# InputCircuits.net
KiCad netlist of a schematic drawn in Altium Designer
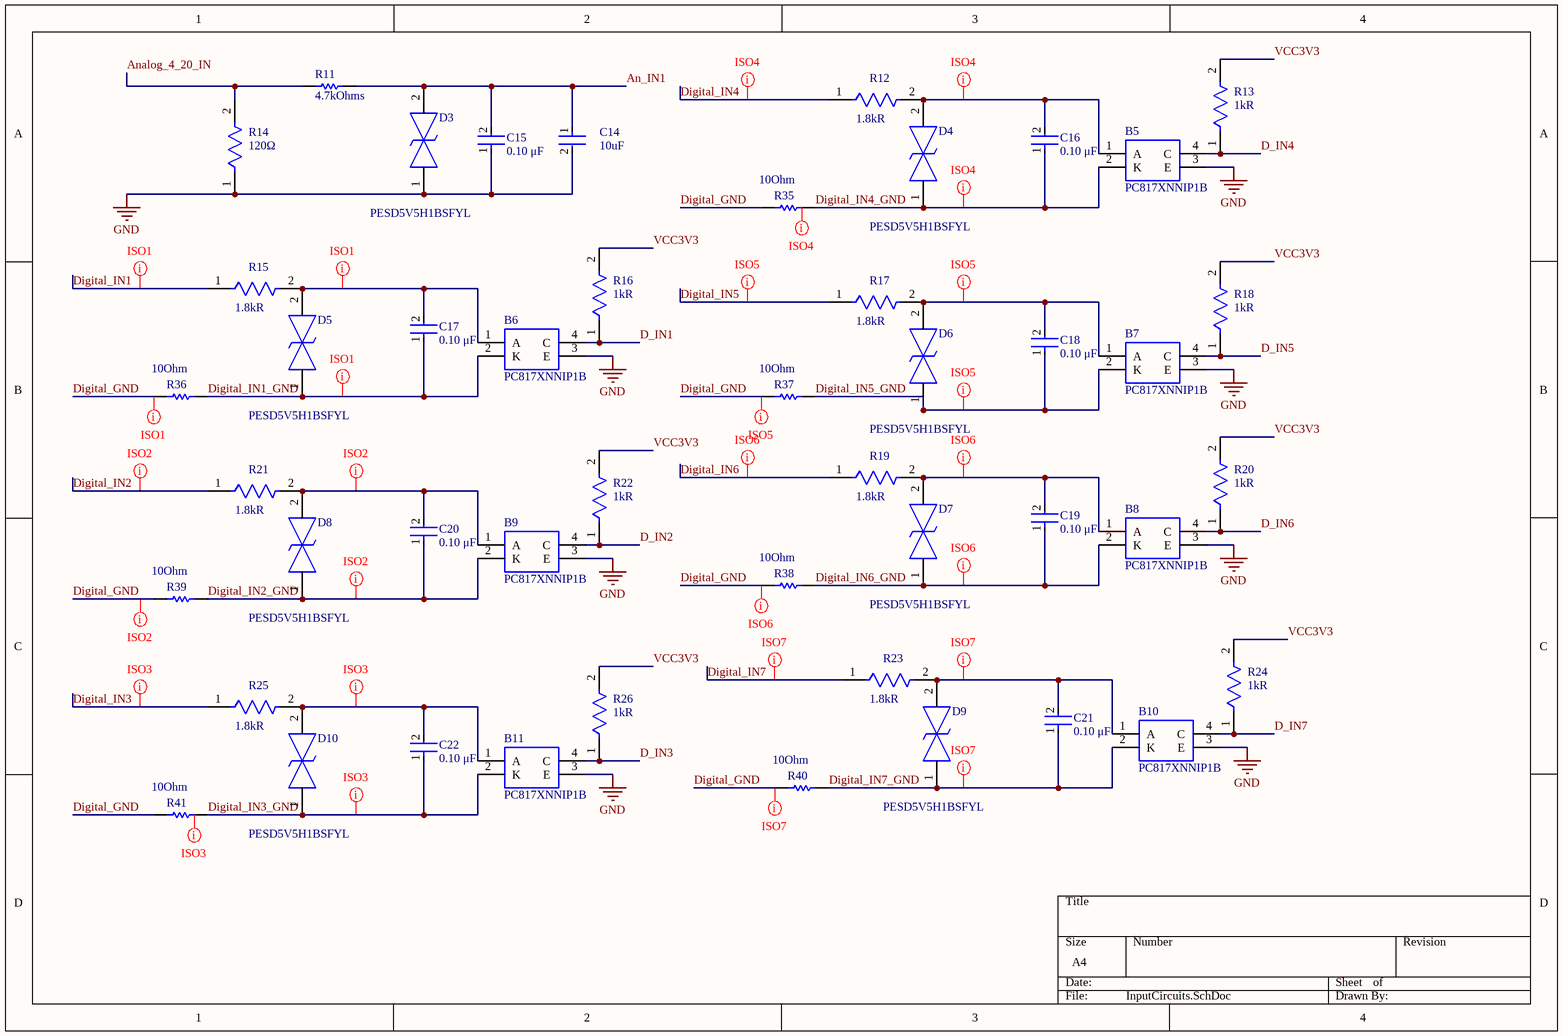
[diagram p0: InputCircuits.SchDoc]

(export (version "E")
  (design (tool "Eeschema 10.0.6"))
  (components
    (comp (ref "B5")
      (value "PC817XNNIP1B")
      (footprint "SOP254P960X420-4N")
      (description "Transistor Output Optocouplers Photocoupler")
      (fields (field (name "MOUSER PART NUMBER") "852-PC817XNNIP1B"))
      (libsource (lib "Schlib2") (part "PC817XNNIP1B"))
    )
    (comp (ref "B6")
      (value "PC817XNNIP1B")
      (footprint "SOP254P960X420-4N")
      (description "Transistor Output Optocouplers Photocoupler")
      (fields (field (name "MOUSER PART NUMBER") "852-PC817XNNIP1B"))
      (libsource (lib "Schlib2") (part "PC817XNNIP1B"))
    )
    (comp (ref "B7")
      (value "PC817XNNIP1B")
      (footprint "SOP254P960X420-4N")
      (description "Transistor Output Optocouplers Photocoupler")
      (fields (field (name "MOUSER PART NUMBER") "852-PC817XNNIP1B"))
      (libsource (lib "Schlib2") (part "PC817XNNIP1B"))
    )
    (comp (ref "B8")
      (value "PC817XNNIP1B")
      (footprint "SOP254P960X420-4N")
      (description "Transistor Output Optocouplers Photocoupler")
      (fields (field (name "MOUSER PART NUMBER") "852-PC817XNNIP1B"))
      (libsource (lib "Schlib2") (part "PC817XNNIP1B"))
    )
    (comp (ref "B9")
      (value "PC817XNNIP1B")
      (footprint "SOP254P960X420-4N")
      (description "Transistor Output Optocouplers Photocoupler")
      (fields (field (name "MOUSER PART NUMBER") "852-PC817XNNIP1B"))
      (libsource (lib "Schlib2") (part "PC817XNNIP1B"))
    )
    (comp (ref "B10")
      (value "PC817XNNIP1B")
      (footprint "SOP254P960X420-4N")
      (description "Transistor Output Optocouplers Photocoupler")
      (fields (field (name "MOUSER PART NUMBER") "852-PC817XNNIP1B"))
      (libsource (lib "Schlib2") (part "PC817XNNIP1B"))
    )
    (comp (ref "B11")
      (value "PC817XNNIP1B")
      (footprint "SOP254P960X420-4N")
      (description "Transistor Output Optocouplers Photocoupler")
      (fields (field (name "MOUSER PART NUMBER") "852-PC817XNNIP1B"))
      (libsource (lib "Schlib2") (part "PC817XNNIP1B"))
    )
    (comp (ref "C14")
      (value "LMK212B7106KG-TD")
      (footprint "FP-MK212G-MFG")
      (description "CAP CER 10UF 10V X7R 0805")
      (fields (field (name "CAPACITANCE") "10uF") (field (name "TOLERANCE") "10%"))
      (libsource (lib "Altium Content Vault") (part "b4654b650e69147ec39a6b967a45e02"))
    )
    (comp (ref "C15")
      (value "0.10 μF")
      (footprint "FP-C0805C-DN-MFG")
      (description "C0805 0.10 μF X7R 30ppm/°C 10.00% 50 V")
      (fields
        (field (name "MANUFACTURER") "KEMET")
        (field (name "MANUFACTURER PART NUMBER") "C0805C104K5RAC7411")
      )
      (libsource (lib "Altium Content Vault") (part "b4654b650e69147ec39a6b967a45e02"))
    )
    (comp (ref "C16")
      (value "0.10 μF")
      (footprint "FP-C0805C-DN-MFG")
      (description "C0805 0.10 μF X7R 30ppm/°C 10.00% 50 V")
      (fields
        (field (name "MANUFACTURER") "KEMET")
        (field (name "MANUFACTURER PART NUMBER") "C0805C104K5RAC7411")
      )
      (libsource (lib "Altium Content Vault") (part "b4654b650e69147ec39a6b967a45e02"))
    )
    (comp (ref "C17")
      (value "0.10 μF")
      (footprint "FP-C0805C-DN-MFG")
      (description "C0805 0.10 μF X7R 30ppm/°C 10.00% 50 V")
      (fields
        (field (name "MANUFACTURER") "KEMET")
        (field (name "MANUFACTURER PART NUMBER") "C0805C104K5RAC7411")
      )
      (libsource (lib "Altium Content Vault") (part "b4654b650e69147ec39a6b967a45e02"))
    )
    (comp (ref "C18")
      (value "0.10 μF")
      (footprint "FP-C0805C-DN-MFG")
      (description "C0805 0.10 μF X7R 30ppm/°C 10.00% 50 V")
      (fields
        (field (name "MANUFACTURER") "KEMET")
        (field (name "MANUFACTURER PART NUMBER") "C0805C104K5RAC7411")
      )
      (libsource (lib "Altium Content Vault") (part "b4654b650e69147ec39a6b967a45e02"))
    )
    (comp (ref "C19")
      (value "0.10 μF")
      (footprint "FP-C0805C-DN-MFG")
      (description "C0805 0.10 μF X7R 30ppm/°C 10.00% 50 V")
      (fields
        (field (name "MANUFACTURER") "KEMET")
        (field (name "MANUFACTURER PART NUMBER") "C0805C104K5RAC7411")
      )
      (libsource (lib "Altium Content Vault") (part "b4654b650e69147ec39a6b967a45e02"))
    )
    (comp (ref "C20")
      (value "0.10 μF")
      (footprint "FP-C0805C-DN-MFG")
      (description "C0805 0.10 μF X7R 30ppm/°C 10.00% 50 V")
      (fields
        (field (name "MANUFACTURER") "KEMET")
        (field (name "MANUFACTURER PART NUMBER") "C0805C104K5RAC7411")
      )
      (libsource (lib "Altium Content Vault") (part "b4654b650e69147ec39a6b967a45e02"))
    )
    (comp (ref "C21")
      (value "0.10 μF")
      (footprint "FP-C0805C-DN-MFG")
      (description "C0805 0.10 μF X7R 30ppm/°C 10.00% 50 V")
      (fields
        (field (name "MANUFACTURER") "KEMET")
        (field (name "MANUFACTURER PART NUMBER") "C0805C104K5RAC7411")
      )
      (libsource (lib "Altium Content Vault") (part "b4654b650e69147ec39a6b967a45e02"))
    )
    (comp (ref "C22")
      (value "0.10 μF")
      (footprint "FP-C0805C-DN-MFG")
      (description "C0805 0.10 μF X7R 30ppm/°C 10.00% 50 V")
      (fields
        (field (name "MANUFACTURER") "KEMET")
        (field (name "MANUFACTURER PART NUMBER") "C0805C104K5RAC7411")
      )
      (libsource (lib "Altium Content Vault") (part "b4654b650e69147ec39a6b967a45e02"))
    )
    (comp (ref "D3")
      (value "PESD5V5H1BSFYL")
      (footprint "PESD5V0H1BSFYL")
      (description "ESD Suppressors / TVS Diodes")
      (fields (field (name "MOUSER PART NUMBER") "771-PESD5V5H1BSFYL"))
      (libsource (lib "Schlib2") (part "PESD5V5H1BSFYL"))
    )
    (comp (ref "D4")
      (value "PESD5V5H1BSFYL")
      (footprint "PESD5V0H1BSFYL")
      (description "ESD Suppressors / TVS Diodes")
      (fields (field (name "MOUSER PART NUMBER") "771-PESD5V5H1BSFYL"))
      (libsource (lib "Schlib2") (part "PESD5V5H1BSFYL"))
    )
    (comp (ref "D5")
      (value "PESD5V5H1BSFYL")
      (footprint "PESD5V0H1BSFYL")
      (description "ESD Suppressors / TVS Diodes")
      (fields (field (name "MOUSER PART NUMBER") "771-PESD5V5H1BSFYL"))
      (libsource (lib "Schlib2") (part "PESD5V5H1BSFYL"))
    )
    (comp (ref "D6")
      (value "PESD5V5H1BSFYL")
      (footprint "PESD5V0H1BSFYL")
      (description "ESD Suppressors / TVS Diodes")
      (fields (field (name "MOUSER PART NUMBER") "771-PESD5V5H1BSFYL"))
      (libsource (lib "Schlib2") (part "PESD5V5H1BSFYL"))
    )
    (comp (ref "D7")
      (value "PESD5V5H1BSFYL")
      (footprint "PESD5V0H1BSFYL")
      (description "ESD Suppressors / TVS Diodes")
      (fields (field (name "MOUSER PART NUMBER") "771-PESD5V5H1BSFYL"))
      (libsource (lib "Schlib2") (part "PESD5V5H1BSFYL"))
    )
    (comp (ref "D8")
      (value "PESD5V5H1BSFYL")
      (footprint "PESD5V0H1BSFYL")
      (description "ESD Suppressors / TVS Diodes")
      (fields (field (name "MOUSER PART NUMBER") "771-PESD5V5H1BSFYL"))
      (libsource (lib "Schlib2") (part "PESD5V5H1BSFYL"))
    )
    (comp (ref "D9")
      (value "PESD5V5H1BSFYL")
      (footprint "PESD5V0H1BSFYL")
      (description "ESD Suppressors / TVS Diodes")
      (fields (field (name "MOUSER PART NUMBER") "771-PESD5V5H1BSFYL"))
      (libsource (lib "Schlib2") (part "PESD5V5H1BSFYL"))
    )
    (comp (ref "D10")
      (value "PESD5V5H1BSFYL")
      (footprint "PESD5V0H1BSFYL")
      (description "ESD Suppressors / TVS Diodes")
      (fields (field (name "MOUSER PART NUMBER") "771-PESD5V5H1BSFYL"))
      (libsource (lib "Schlib2") (part "PESD5V5H1BSFYL"))
    )
    (comp (ref "R11")
      (value "RC0603FR-074K7L")
      (footprint "RESC1608X55X25LL10T15")
      (description "Chip Resistor, 4.7 KOhm, +/- 1%, 0.1 W, -55 to 155 degC, 0603 (1608 Metric), RoHS, Tape and Reel")
      (fields
        (field (name "MANUFACTURER") "Yageo")
        (field (name "RESISTANCE") "4.7kOhms")
        (field (name "TOLERANCE") "1%")
      )
      (libsource (lib "Altium Content Vault") (part "RES-2"))
    )
    (comp (ref "R12")
      (value "RC0603FR-071K8L")
      (footprint "FP-RC0603-0_55-IPC_C")
      (description "RES SMD 1.8K OHM 1% 1/10W 0603")
      (fields (field (name "TOLERANCE") "1%") (field (name "RESISTANCE") "1.8kR"))
      (libsource (lib "Altium Content Vault") (part "1029c3af85768c4190bb7ad29bc67b5"))
    )
    (comp (ref "R13")
      (value "RC0603FR-071KL")
      (footprint "FP-RC0603-0_55-IPC_C")
      (description "RES 1K OHM 1% 1/10W 0603")
      (fields (field (name "RESISTANCE") "1kR") (field (name "TOLERANCE") "1%"))
      (libsource (lib "Altium Content Vault") (part "1029c3af85768c4190bb7ad29bc67b5"))
    )
    (comp (ref "R14")
      (value "RT1206FRE07120RL")
      (footprint "FP-RT1206-MFG")
      (description "RES SMD 120 OHM 1% 1/4W 1206")
      (fields
        (field (name "RESISTANCE") "120Ω")
        (field (name "OCTOPART") "https://octopart.com/rt1206fre07120rl-yageo-1433320")
        (field (name "TOLERANCE") "0.0002")
      )
      (libsource (lib "Altium Content Vault") (part "1029c3af85768c4190bb7ad29bc67b5"))
    )
    (comp (ref "R15")
      (value "RC0603FR-071K8L")
      (footprint "FP-RC0603-0_55-IPC_C")
      (description "RES SMD 1.8K OHM 1% 1/10W 0603")
      (fields (field (name "TOLERANCE") "1%") (field (name "RESISTANCE") "1.8kR"))
      (libsource (lib "Altium Content Vault") (part "1029c3af85768c4190bb7ad29bc67b5"))
    )
    (comp (ref "R16")
      (value "RC0603FR-071KL")
      (footprint "FP-RC0603-0_55-IPC_C")
      (description "RES 1K OHM 1% 1/10W 0603")
      (fields (field (name "RESISTANCE") "1kR") (field (name "TOLERANCE") "1%"))
      (libsource (lib "Altium Content Vault") (part "1029c3af85768c4190bb7ad29bc67b5"))
    )
    (comp (ref "R17")
      (value "RC0603FR-071K8L")
      (footprint "FP-RC0603-0_55-IPC_C")
      (description "RES SMD 1.8K OHM 1% 1/10W 0603")
      (fields (field (name "TOLERANCE") "1%") (field (name "RESISTANCE") "1.8kR"))
      (libsource (lib "Altium Content Vault") (part "1029c3af85768c4190bb7ad29bc67b5"))
    )
    (comp (ref "R18")
      (value "RC0603FR-071KL")
      (footprint "FP-RC0603-0_55-IPC_C")
      (description "RES 1K OHM 1% 1/10W 0603")
      (fields (field (name "RESISTANCE") "1kR") (field (name "TOLERANCE") "1%"))
      (libsource (lib "Altium Content Vault") (part "1029c3af85768c4190bb7ad29bc67b5"))
    )
    (comp (ref "R19")
      (value "RC0603FR-071K8L")
      (footprint "FP-RC0603-0_55-IPC_C")
      (description "RES SMD 1.8K OHM 1% 1/10W 0603")
      (fields (field (name "TOLERANCE") "1%") (field (name "RESISTANCE") "1.8kR"))
      (libsource (lib "Altium Content Vault") (part "1029c3af85768c4190bb7ad29bc67b5"))
    )
    (comp (ref "R20")
      (value "RC0603FR-071KL")
      (footprint "FP-RC0603-0_55-IPC_C")
      (description "RES 1K OHM 1% 1/10W 0603")
      (fields (field (name "RESISTANCE") "1kR") (field (name "TOLERANCE") "1%"))
      (libsource (lib "Altium Content Vault") (part "1029c3af85768c4190bb7ad29bc67b5"))
    )
    (comp (ref "R21")
      (value "RC0603FR-071K8L")
      (footprint "FP-RC0603-0_55-IPC_C")
      (description "RES SMD 1.8K OHM 1% 1/10W 0603")
      (fields (field (name "TOLERANCE") "1%") (field (name "RESISTANCE") "1.8kR"))
      (libsource (lib "Altium Content Vault") (part "1029c3af85768c4190bb7ad29bc67b5"))
    )
    (comp (ref "R22")
      (value "RC0603FR-071KL")
      (footprint "FP-RC0603-0_55-IPC_C")
      (description "RES 1K OHM 1% 1/10W 0603")
      (fields (field (name "RESISTANCE") "1kR") (field (name "TOLERANCE") "1%"))
      (libsource (lib "Altium Content Vault") (part "1029c3af85768c4190bb7ad29bc67b5"))
    )
    (comp (ref "R23")
      (value "RC0603FR-071K8L")
      (footprint "FP-RC0603-0_55-IPC_C")
      (description "RES SMD 1.8K OHM 1% 1/10W 0603")
      (fields (field (name "TOLERANCE") "1%") (field (name "RESISTANCE") "1.8kR"))
      (libsource (lib "Altium Content Vault") (part "1029c3af85768c4190bb7ad29bc67b5"))
    )
    (comp (ref "R24")
      (value "RC0603FR-071KL")
      (footprint "FP-RC0603-0_55-IPC_C")
      (description "RES 1K OHM 1% 1/10W 0603")
      (fields (field (name "RESISTANCE") "1kR") (field (name "TOLERANCE") "1%"))
      (libsource (lib "Altium Content Vault") (part "1029c3af85768c4190bb7ad29bc67b5"))
    )
    (comp (ref "R25")
      (value "RC0603FR-071K8L")
      (footprint "FP-RC0603-0_55-IPC_C")
      (description "RES SMD 1.8K OHM 1% 1/10W 0603")
      (fields (field (name "TOLERANCE") "1%") (field (name "RESISTANCE") "1.8kR"))
      (libsource (lib "Altium Content Vault") (part "1029c3af85768c4190bb7ad29bc67b5"))
    )
    (comp (ref "R26")
      (value "RC0603FR-071KL")
      (footprint "FP-RC0603-0_55-IPC_C")
      (description "RES 1K OHM 1% 1/10W 0603")
      (fields (field (name "RESISTANCE") "1kR") (field (name "TOLERANCE") "1%"))
      (libsource (lib "Altium Content Vault") (part "1029c3af85768c4190bb7ad29bc67b5"))
    )
    (comp (ref "R35")
      (value "RC0805FR-0710RL")
      (footprint "RESC2013X60X35ML10T20")
      (description "Chip Resistor, 10 Ohm, +/- 1%, 0.125 W, -55 to 155 degC, 0805 (2012 Metric), RoHS, Tape and Reel")
      (fields
        (field (name "RESISTANCE") "10Ohm")
        (field (name "MANUFACTURER") "Yageo")
        (field (name "TOLERANCE") "1%")
      )
      (libsource (lib "Altium Content Vault") (part "RES-2"))
    )
    (comp (ref "R36")
      (value "RC0805FR-0710RL")
      (footprint "RESC2013X60X35ML10T20")
      (description "Chip Resistor, 10 Ohm, +/- 1%, 0.125 W, -55 to 155 degC, 0805 (2012 Metric), RoHS, Tape and Reel")
      (fields
        (field (name "RESISTANCE") "10Ohm")
        (field (name "MANUFACTURER") "Yageo")
        (field (name "TOLERANCE") "1%")
      )
      (libsource (lib "Altium Content Vault") (part "RES-2"))
    )
    (comp (ref "R37")
      (value "RC0805FR-0710RL")
      (footprint "RESC2013X60X35ML10T20")
      (description "Chip Resistor, 10 Ohm, +/- 1%, 0.125 W, -55 to 155 degC, 0805 (2012 Metric), RoHS, Tape and Reel")
      (fields
        (field (name "RESISTANCE") "10Ohm")
        (field (name "MANUFACTURER") "Yageo")
        (field (name "TOLERANCE") "1%")
      )
      (libsource (lib "Altium Content Vault") (part "RES-2"))
    )
    (comp (ref "R38")
      (value "RC0805FR-0710RL")
      (footprint "RESC2013X60X35ML10T20")
      (description "Chip Resistor, 10 Ohm, +/- 1%, 0.125 W, -55 to 155 degC, 0805 (2012 Metric), RoHS, Tape and Reel")
      (fields
        (field (name "RESISTANCE") "10Ohm")
        (field (name "MANUFACTURER") "Yageo")
        (field (name "TOLERANCE") "1%")
      )
      (libsource (lib "Altium Content Vault") (part "RES-2"))
    )
    (comp (ref "R39")
      (value "RC0805FR-0710RL")
      (footprint "RESC2013X60X35ML10T20")
      (description "Chip Resistor, 10 Ohm, +/- 1%, 0.125 W, -55 to 155 degC, 0805 (2012 Metric), RoHS, Tape and Reel")
      (fields
        (field (name "RESISTANCE") "10Ohm")
        (field (name "MANUFACTURER") "Yageo")
        (field (name "TOLERANCE") "1%")
      )
      (libsource (lib "Altium Content Vault") (part "RES-2"))
    )
    (comp (ref "R40")
      (value "RC0805FR-0710RL")
      (footprint "RESC2013X60X35ML10T20")
      (description "Chip Resistor, 10 Ohm, +/- 1%, 0.125 W, -55 to 155 degC, 0805 (2012 Metric), RoHS, Tape and Reel")
      (fields
        (field (name "RESISTANCE") "10Ohm")
        (field (name "MANUFACTURER") "Yageo")
        (field (name "TOLERANCE") "1%")
      )
      (libsource (lib "Altium Content Vault") (part "RES-2"))
    )
    (comp (ref "R41")
      (value "RC0805FR-0710RL")
      (footprint "RESC2013X60X35ML10T20")
      (description "Chip Resistor, 10 Ohm, +/- 1%, 0.125 W, -55 to 155 degC, 0805 (2012 Metric), RoHS, Tape and Reel")
      (fields
        (field (name "RESISTANCE") "10Ohm")
        (field (name "MANUFACTURER") "Yageo")
        (field (name "TOLERANCE") "1%")
      )
      (libsource (lib "Altium Content Vault") (part "RES-2"))
    )
  )
  (nets
    (net (code "1") (name "/An_IN1") (class "Default")
      (node (ref "C14") (pin "1") (pinfunction "1_1") (pintype "passive"))
      (node (ref "C15") (pin "2") (pinfunction "2_2") (pintype "passive"))
      (node (ref "D3") (pin "2") (pinfunction "2_2") (pintype "passive"))
      (node (ref "R11") (pin "1") (pinfunction "1_1") (pintype "passive"))
    )
    (net (code "2") (name "/Analog_4_20_IN") (class "Default")
      (node (ref "R11") (pin "2") (pinfunction "2_2") (pintype "passive"))
      (node (ref "R14") (pin "2") (pinfunction "2_2") (pintype "passive"))
    )
    (net (code "3") (name "/D_IN1") (class "Default")
      (node (ref "B6") (pin "4") (pinfunction "C_4") (pintype "passive"))
      (node (ref "R16") (pin "1") (pinfunction "1_1") (pintype "passive"))
    )
    (net (code "4") (name "/D_IN2") (class "Default")
      (node (ref "B9") (pin "4") (pinfunction "C_4") (pintype "passive"))
      (node (ref "R22") (pin "1") (pinfunction "1_1") (pintype "passive"))
    )
    (net (code "5") (name "/D_IN3") (class "Default")
      (node (ref "B11") (pin "4") (pinfunction "C_4") (pintype "passive"))
      (node (ref "R26") (pin "1") (pinfunction "1_1") (pintype "passive"))
    )
    (net (code "6") (name "/D_IN4") (class "Default")
      (node (ref "B5") (pin "4") (pinfunction "C_4") (pintype "passive"))
      (node (ref "R13") (pin "1") (pinfunction "1_1") (pintype "passive"))
    )
    (net (code "7") (name "/D_IN5") (class "Default")
      (node (ref "B7") (pin "4") (pinfunction "C_4") (pintype "passive"))
      (node (ref "R18") (pin "1") (pinfunction "1_1") (pintype "passive"))
    )
    (net (code "8") (name "/D_IN6") (class "Default")
      (node (ref "B8") (pin "4") (pinfunction "C_4") (pintype "passive"))
      (node (ref "R20") (pin "1") (pinfunction "1_1") (pintype "passive"))
    )
    (net (code "9") (name "/D_IN7") (class "Default")
      (node (ref "B10") (pin "4") (pinfunction "C_4") (pintype "passive"))
      (node (ref "R24") (pin "1") (pinfunction "1_1") (pintype "passive"))
    )
    (net (code "10") (name "/Digital_GND") (class "Default")
      (node (ref "R35") (pin "1") (pinfunction "1_1") (pintype "passive"))
      (node (ref "R36") (pin "1") (pinfunction "1_1") (pintype "passive"))
      (node (ref "R37") (pin "1") (pinfunction "1_1") (pintype "passive"))
      (node (ref "R38") (pin "1") (pinfunction "1_1") (pintype "passive"))
      (node (ref "R39") (pin "1") (pinfunction "1_1") (pintype "passive"))
      (node (ref "R40") (pin "1") (pinfunction "1_1") (pintype "passive"))
      (node (ref "R41") (pin "1") (pinfunction "1_1") (pintype "passive"))
    )
    (net (code "11") (name "/Digital_IN1") (class "Default")
      (node (ref "R15") (pin "1") (pinfunction "1_1") (pintype "passive"))
    )
    (net (code "12") (name "/Digital_IN1_GND") (class "Default")
      (node (ref "B6") (pin "2") (pinfunction "K_2") (pintype "passive"))
      (node (ref "C17") (pin "1") (pinfunction "1_1") (pintype "passive"))
      (node (ref "D5") (pin "1") (pinfunction "1_1") (pintype "passive"))
      (node (ref "R36") (pin "2") (pinfunction "2_2") (pintype "passive"))
    )
    (net (code "13") (name "/Digital_IN2") (class "Default")
      (node (ref "R21") (pin "1") (pinfunction "1_1") (pintype "passive"))
    )
    (net (code "14") (name "/Digital_IN2_GND") (class "Default")
      (node (ref "B9") (pin "2") (pinfunction "K_2") (pintype "passive"))
      (node (ref "C20") (pin "1") (pinfunction "1_1") (pintype "passive"))
      (node (ref "D8") (pin "1") (pinfunction "1_1") (pintype "passive"))
      (node (ref "R39") (pin "2") (pinfunction "2_2") (pintype "passive"))
    )
    (net (code "15") (name "/Digital_IN3") (class "Default")
      (node (ref "R25") (pin "1") (pinfunction "1_1") (pintype "passive"))
    )
    (net (code "16") (name "/Digital_IN3_GND") (class "Default")
      (node (ref "B11") (pin "2") (pinfunction "K_2") (pintype "passive"))
      (node (ref "C22") (pin "1") (pinfunction "1_1") (pintype "passive"))
      (node (ref "D10") (pin "1") (pinfunction "1_1") (pintype "passive"))
      (node (ref "R41") (pin "2") (pinfunction "2_2") (pintype "passive"))
    )
    (net (code "17") (name "/Digital_IN4") (class "Default")
      (node (ref "R12") (pin "1") (pinfunction "1_1") (pintype "passive"))
    )
    (net (code "18") (name "/Digital_IN4_GND") (class "Default")
      (node (ref "B5") (pin "2") (pinfunction "K_2") (pintype "passive"))
      (node (ref "C16") (pin "1") (pinfunction "1_1") (pintype "passive"))
      (node (ref "D4") (pin "1") (pinfunction "1_1") (pintype "passive"))
      (node (ref "R35") (pin "2") (pinfunction "2_2") (pintype "passive"))
    )
    (net (code "19") (name "/Digital_IN5") (class "Default")
      (node (ref "R17") (pin "1") (pinfunction "1_1") (pintype "passive"))
    )
    (net (code "20") (name "/Digital_IN5_GND") (class "Default")
      (node (ref "B7") (pin "2") (pinfunction "K_2") (pintype "passive"))
      (node (ref "C18") (pin "1") (pinfunction "1_1") (pintype "passive"))
      (node (ref "D6") (pin "1") (pinfunction "1_1") (pintype "passive"))
      (node (ref "R37") (pin "2") (pinfunction "2_2") (pintype "passive"))
    )
    (net (code "21") (name "/Digital_IN6") (class "Default")
      (node (ref "R19") (pin "1") (pinfunction "1_1") (pintype "passive"))
    )
    (net (code "22") (name "/Digital_IN6_GND") (class "Default")
      (node (ref "B8") (pin "2") (pinfunction "K_2") (pintype "passive"))
      (node (ref "C19") (pin "1") (pinfunction "1_1") (pintype "passive"))
      (node (ref "D7") (pin "1") (pinfunction "1_1") (pintype "passive"))
      (node (ref "R38") (pin "2") (pinfunction "2_2") (pintype "passive"))
    )
    (net (code "23") (name "/Digital_IN7") (class "Default")
      (node (ref "R23") (pin "1") (pinfunction "1_1") (pintype "passive"))
    )
    (net (code "24") (name "/Digital_IN7_GND") (class "Default")
      (node (ref "B10") (pin "2") (pinfunction "K_2") (pintype "passive"))
      (node (ref "C21") (pin "1") (pinfunction "1_1") (pintype "passive"))
      (node (ref "D9") (pin "1") (pinfunction "1_1") (pintype "passive"))
      (node (ref "R40") (pin "2") (pinfunction "2_2") (pintype "passive"))
    )
    (net (code "25") (name "/VCC3V3") (class "Default")
      (node (ref "R13") (pin "2") (pinfunction "2_2") (pintype "passive"))
      (node (ref "R16") (pin "2") (pinfunction "2_2") (pintype "passive"))
      (node (ref "R18") (pin "2") (pinfunction "2_2") (pintype "passive"))
      (node (ref "R20") (pin "2") (pinfunction "2_2") (pintype "passive"))
      (node (ref "R22") (pin "2") (pinfunction "2_2") (pintype "passive"))
      (node (ref "R24") (pin "2") (pinfunction "2_2") (pintype "passive"))
      (node (ref "R26") (pin "2") (pinfunction "2_2") (pintype "passive"))
    )
    (net (code "26") (name "GND") (class "Default")
      (node (ref "B10") (pin "3") (pinfunction "E_3") (pintype "passive"))
      (node (ref "B11") (pin "3") (pinfunction "E_3") (pintype "passive"))
      (node (ref "B5") (pin "3") (pinfunction "E_3") (pintype "passive"))
      (node (ref "B6") (pin "3") (pinfunction "E_3") (pintype "passive"))
      (node (ref "B7") (pin "3") (pinfunction "E_3") (pintype "passive"))
      (node (ref "B8") (pin "3") (pinfunction "E_3") (pintype "passive"))
      (node (ref "B9") (pin "3") (pinfunction "E_3") (pintype "passive"))
      (node (ref "C14") (pin "2") (pinfunction "2_2") (pintype "passive"))
      (node (ref "C15") (pin "1") (pinfunction "1_1") (pintype "passive"))
      (node (ref "D3") (pin "1") (pinfunction "1_1") (pintype "passive"))
      (node (ref "R14") (pin "1") (pinfunction "1_1") (pintype "passive"))
    )
    (net (code "27") (name "Net-(B5-A)") (class "Default")
      (node (ref "B5") (pin "1") (pinfunction "A_1") (pintype "passive"))
      (node (ref "C16") (pin "2") (pinfunction "2_2") (pintype "passive"))
      (node (ref "D4") (pin "2") (pinfunction "2_2") (pintype "passive"))
      (node (ref "R12") (pin "2") (pinfunction "2_2") (pintype "passive"))
    )
    (net (code "28") (name "Net-(B6-A)") (class "Default")
      (node (ref "B6") (pin "1") (pinfunction "A_1") (pintype "passive"))
      (node (ref "C17") (pin "2") (pinfunction "2_2") (pintype "passive"))
      (node (ref "D5") (pin "2") (pinfunction "2_2") (pintype "passive"))
      (node (ref "R15") (pin "2") (pinfunction "2_2") (pintype "passive"))
    )
    (net (code "29") (name "Net-(B7-A)") (class "Default")
      (node (ref "B7") (pin "1") (pinfunction "A_1") (pintype "passive"))
      (node (ref "C18") (pin "2") (pinfunction "2_2") (pintype "passive"))
      (node (ref "D6") (pin "2") (pinfunction "2_2") (pintype "passive"))
      (node (ref "R17") (pin "2") (pinfunction "2_2") (pintype "passive"))
    )
    (net (code "30") (name "Net-(B8-A)") (class "Default")
      (node (ref "B8") (pin "1") (pinfunction "A_1") (pintype "passive"))
      (node (ref "C19") (pin "2") (pinfunction "2_2") (pintype "passive"))
      (node (ref "D7") (pin "2") (pinfunction "2_2") (pintype "passive"))
      (node (ref "R19") (pin "2") (pinfunction "2_2") (pintype "passive"))
    )
    (net (code "31") (name "Net-(B9-A)") (class "Default")
      (node (ref "B9") (pin "1") (pinfunction "A_1") (pintype "passive"))
      (node (ref "C20") (pin "2") (pinfunction "2_2") (pintype "passive"))
      (node (ref "D8") (pin "2") (pinfunction "2_2") (pintype "passive"))
      (node (ref "R21") (pin "2") (pinfunction "2_2") (pintype "passive"))
    )
    (net (code "32") (name "Net-(B10-A)") (class "Default")
      (node (ref "B10") (pin "1") (pinfunction "A_1") (pintype "passive"))
      (node (ref "C21") (pin "2") (pinfunction "2_2") (pintype "passive"))
      (node (ref "D9") (pin "2") (pinfunction "2_2") (pintype "passive"))
      (node (ref "R23") (pin "2") (pinfunction "2_2") (pintype "passive"))
    )
    (net (code "33") (name "Net-(B11-A)") (class "Default")
      (node (ref "B11") (pin "1") (pinfunction "A_1") (pintype "passive"))
      (node (ref "C22") (pin "2") (pinfunction "2_2") (pintype "passive"))
      (node (ref "D10") (pin "2") (pinfunction "2_2") (pintype "passive"))
      (node (ref "R25") (pin "2") (pinfunction "2_2") (pintype "passive"))
    )
  )
)
